# RGB_Camera.net
KiCad netlist of a schematic drawn in Altium Designer
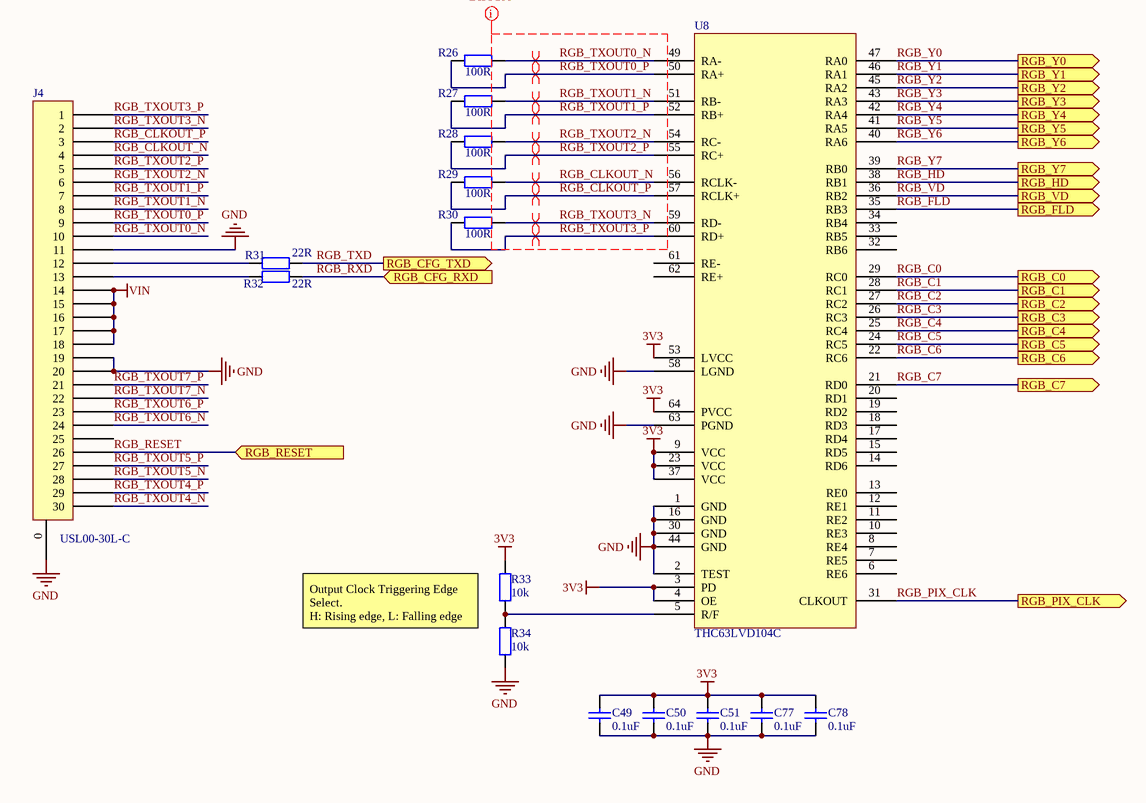
[diagram p0: RGB_Camera.SchDoc]

(export (version "E")
  (design (tool "Eeschema 10.0.6"))
  (components
    (comp (ref "C49")
      (value "GRM155R71C104KA88D")
      (footprint "0402C_M")
      (description "CAP CER 0.1UF 16V X7R 0402")
      (fields
        (field (name "MANUFACTURER") "Murata Electronics North America")
        (field (name "TOLERANCE") "±10%")
        (field (name "CAPACITANCE") "0.1uF")
      )
      (libsource (lib "KMTI-main") (part "GRM155R71C104KA88D"))
    )
    (comp (ref "C50")
      (value "GRM155R71C104KA88D")
      (footprint "0402C_M")
      (description "CAP CER 0.1UF 16V X7R 0402")
      (fields
        (field (name "MANUFACTURER") "Murata Electronics North America")
        (field (name "TOLERANCE") "±10%")
        (field (name "CAPACITANCE") "0.1uF")
      )
      (libsource (lib "KMTI-main") (part "GRM155R71C104KA88D"))
    )
    (comp (ref "C51")
      (value "GRM155R71C104KA88D")
      (footprint "0402C_M")
      (description "CAP CER 0.1UF 16V X7R 0402")
      (fields
        (field (name "MANUFACTURER") "Murata Electronics North America")
        (field (name "TOLERANCE") "±10%")
        (field (name "CAPACITANCE") "0.1uF")
      )
      (libsource (lib "KMTI-main") (part "GRM155R71C104KA88D"))
    )
    (comp (ref "C77")
      (value "GRM155R71C104KA88D")
      (footprint "0402C_M")
      (description "CAP CER 0.1UF 16V X7R 0402")
      (fields
        (field (name "MANUFACTURER") "Murata Electronics North America")
        (field (name "TOLERANCE") "±10%")
        (field (name "CAPACITANCE") "0.1uF")
      )
      (libsource (lib "KMTI-main") (part "GRM155R71C104KA88D"))
    )
    (comp (ref "C78")
      (value "GRM155R71C104KA88D")
      (footprint "0402C_M")
      (description "CAP CER 0.1UF 16V X7R 0402")
      (fields
        (field (name "MANUFACTURER") "Murata Electronics North America")
        (field (name "TOLERANCE") "±10%")
        (field (name "CAPACITANCE") "0.1uF")
      )
      (libsource (lib "KMTI-main") (part "GRM155R71C104KA88D"))
    )
    (comp (ref "J4")
      (value "USL00-30L-C")
      (footprint "USL00-30L-C")
      (libsource (lib "KMTI-main") (part "USL00-30L-C"))
    )
    (comp (ref "R26")
      (value "100R")
      (footprint "0402R_M")
      (description "RES SMD 100 OHM 1% 1/16W 0402")
      (fields
        (field (name "MANUFACTURER") "Vishay Dale")
        (field (name "MANUFACTURER PART NUMBER") "CRCW0402100RFKEE")
      )
      (libsource (lib "KMTI-main") (part "CRCW0402100RFKEE"))
    )
    (comp (ref "R27")
      (value "100R")
      (footprint "0402R_M")
      (description "RES SMD 100 OHM 1% 1/16W 0402")
      (fields
        (field (name "MANUFACTURER") "Vishay Dale")
        (field (name "MANUFACTURER PART NUMBER") "CRCW0402100RFKEE")
      )
      (libsource (lib "KMTI-main") (part "CRCW0402100RFKEE"))
    )
    (comp (ref "R28")
      (value "100R")
      (footprint "0402R_M")
      (description "RES SMD 100 OHM 1% 1/16W 0402")
      (fields
        (field (name "MANUFACTURER") "Vishay Dale")
        (field (name "MANUFACTURER PART NUMBER") "CRCW0402100RFKEE")
      )
      (libsource (lib "KMTI-main") (part "CRCW0402100RFKEE"))
    )
    (comp (ref "R29")
      (value "100R")
      (footprint "0402R_M")
      (description "RES SMD 100 OHM 1% 1/16W 0402")
      (fields
        (field (name "MANUFACTURER") "Vishay Dale")
        (field (name "MANUFACTURER PART NUMBER") "CRCW0402100RFKEE")
      )
      (libsource (lib "KMTI-main") (part "CRCW0402100RFKEE"))
    )
    (comp (ref "R30")
      (value "100R")
      (footprint "0402R_M")
      (description "RES SMD 100 OHM 1% 1/16W 0402")
      (fields
        (field (name "MANUFACTURER") "Vishay Dale")
        (field (name "MANUFACTURER PART NUMBER") "CRCW0402100RFKEE")
      )
      (libsource (lib "KMTI-main") (part "CRCW0402100RFKEE"))
    )
    (comp (ref "R31")
      (value "CRCW040222R0JNED")
      (footprint "0402R_M")
      (description "RES SMD 22 OHM 5% 1/16W 0402")
      (fields
        (field (name "MANUFACTURER") "Vishay / Dale")
        (field (name "TOLERANCE") "5 %")
        (field (name "RESISTANCE") "22R")
      )
      (libsource (lib "KMTI-main") (part "CRCW040222R0JNED"))
    )
    (comp (ref "R32")
      (value "CRCW040222R0JNED")
      (footprint "0402R_M")
      (description "RES SMD 22 OHM 5% 1/16W 0402")
      (fields
        (field (name "MANUFACTURER") "Vishay / Dale")
        (field (name "TOLERANCE") "5 %")
        (field (name "RESISTANCE") "22R")
      )
      (libsource (lib "KMTI-main") (part "CRCW040222R0JNED"))
    )
    (comp (ref "R33")
      (value "10k")
      (footprint "0402R_M")
      (description "RES SMD 10K OHM 1% 1/16W 0402")
      (fields
        (field (name "MANUFACTURER") "Vishay Dale")
        (field (name "MANUFACTURER PART NUMBER") "CRCW040210K0FKED")
      )
      (libsource (lib "KMTI-main") (part "CRCW040210K0FKED"))
    )
    (comp (ref "R34")
      (value "10k")
      (footprint "0402R_M")
      (description "RES SMD 10K OHM 1% 1/16W 0402")
      (fields
        (field (name "MANUFACTURER") "Vishay Dale")
        (field (name "MANUFACTURER PART NUMBER") "CRCW040210K0FKED")
      )
      (libsource (lib "KMTI-main") (part "CRCW040210K0FKED"))
    )
    (comp (ref "U8")
      (value "THC63LVD104C")
      (footprint "THC_LQFP64_L")
      (description "IC DESERIALIZER SNGL LVDS 64TQFP")
      (fields (field (name "MANUFACTURER") "CEL"))
      (libsource (lib "KMTI-main") (part "THC63LVD104C"))
    )
  )
  (nets
    (net (code "1") (name "/RGB_C0") (class "Default")
      (node (ref "U8") (pin "29") (pinfunction "RC0_29") (pintype "passive"))
    )
    (net (code "2") (name "/RGB_C1") (class "Default")
      (node (ref "U8") (pin "28") (pinfunction "RC1_28") (pintype "passive"))
    )
    (net (code "3") (name "/RGB_C2") (class "Default")
      (node (ref "U8") (pin "27") (pinfunction "RC2_27") (pintype "passive"))
    )
    (net (code "4") (name "/RGB_C3") (class "Default")
      (node (ref "U8") (pin "26") (pinfunction "RC3_26") (pintype "passive"))
    )
    (net (code "5") (name "/RGB_C4") (class "Default")
      (node (ref "U8") (pin "25") (pinfunction "RC4_25") (pintype "passive"))
    )
    (net (code "6") (name "/RGB_C5") (class "Default")
      (node (ref "U8") (pin "24") (pinfunction "RC5_24") (pintype "passive"))
    )
    (net (code "7") (name "/RGB_C6") (class "Default")
      (node (ref "U8") (pin "22") (pinfunction "RC6_22") (pintype "passive"))
    )
    (net (code "8") (name "/RGB_C7") (class "Default")
      (node (ref "U8") (pin "21") (pinfunction "RD0_21") (pintype "passive"))
    )
    (net (code "9") (name "/RGB_CLKOUT_N") (class "Default")
      (node (ref "J4") (pin "4") (pinfunction "4_4") (pintype "passive"))
      (node (ref "R29") (pin "2") (pinfunction "2_2") (pintype "passive"))
      (node (ref "U8") (pin "56") (pinfunction "RCLK-_56") (pintype "passive"))
    )
    (net (code "10") (name "/RGB_CLKOUT_P") (class "Default")
      (node (ref "J4") (pin "3") (pinfunction "3_3") (pintype "passive"))
      (node (ref "R29") (pin "1") (pinfunction "1_1") (pintype "passive"))
      (node (ref "U8") (pin "57") (pinfunction "RCLK+_57") (pintype "passive"))
    )
    (net (code "11") (name "/RGB_FLD") (class "Default")
      (node (ref "U8") (pin "35") (pinfunction "RB3_35") (pintype "passive"))
    )
    (net (code "12") (name "/RGB_HD") (class "Default")
      (node (ref "U8") (pin "38") (pinfunction "RB1_38") (pintype "passive"))
    )
    (net (code "13") (name "/RGB_PIX_CLK") (class "Default")
      (node (ref "U8") (pin "31") (pinfunction "CLKOUT_31") (pintype "passive"))
    )
    (net (code "14") (name "/RGB_RESET") (class "Default")
      (node (ref "J4") (pin "26") (pinfunction "26_26") (pintype "passive"))
    )
    (net (code "15") (name "/RGB_RXD") (class "Default")
      (node (ref "R32") (pin "2") (pinfunction "2_2") (pintype "passive"))
    )
    (net (code "16") (name "/RGB_TXD") (class "Default")
      (node (ref "R31") (pin "2") (pinfunction "2_2") (pintype "passive"))
    )
    (net (code "17") (name "/RGB_TXOUT0_N") (class "Default")
      (node (ref "J4") (pin "10") (pinfunction "10_10") (pintype "passive"))
      (node (ref "R26") (pin "2") (pinfunction "2_2") (pintype "passive"))
      (node (ref "U8") (pin "49") (pinfunction "RA-_49") (pintype "passive"))
    )
    (net (code "18") (name "/RGB_TXOUT0_P") (class "Default")
      (node (ref "J4") (pin "9") (pinfunction "9_9") (pintype "passive"))
      (node (ref "R26") (pin "1") (pinfunction "1_1") (pintype "passive"))
      (node (ref "U8") (pin "50") (pinfunction "RA+_50") (pintype "passive"))
    )
    (net (code "19") (name "/RGB_TXOUT1_N") (class "Default")
      (node (ref "J4") (pin "8") (pinfunction "8_8") (pintype "passive"))
      (node (ref "R27") (pin "2") (pinfunction "2_2") (pintype "passive"))
      (node (ref "U8") (pin "51") (pinfunction "RB-_51") (pintype "passive"))
    )
    (net (code "20") (name "/RGB_TXOUT1_P") (class "Default")
      (node (ref "J4") (pin "7") (pinfunction "7_7") (pintype "passive"))
      (node (ref "R27") (pin "1") (pinfunction "1_1") (pintype "passive"))
      (node (ref "U8") (pin "52") (pinfunction "RB+_52") (pintype "passive"))
    )
    (net (code "21") (name "/RGB_TXOUT2_N") (class "Default")
      (node (ref "J4") (pin "6") (pinfunction "6_6") (pintype "passive"))
      (node (ref "R28") (pin "2") (pinfunction "2_2") (pintype "passive"))
      (node (ref "U8") (pin "54") (pinfunction "RC-_54") (pintype "passive"))
    )
    (net (code "22") (name "/RGB_TXOUT2_P") (class "Default")
      (node (ref "J4") (pin "5") (pinfunction "5_5") (pintype "passive"))
      (node (ref "R28") (pin "1") (pinfunction "1_1") (pintype "passive"))
      (node (ref "U8") (pin "55") (pinfunction "RC+_55") (pintype "passive"))
    )
    (net (code "23") (name "/RGB_TXOUT3_N") (class "Default")
      (node (ref "J4") (pin "2") (pinfunction "2_2") (pintype "passive"))
      (node (ref "R30") (pin "2") (pinfunction "2_2") (pintype "passive"))
      (node (ref "U8") (pin "59") (pinfunction "RD-_59") (pintype "passive"))
    )
    (net (code "24") (name "/RGB_TXOUT3_P") (class "Default")
      (node (ref "J4") (pin "1") (pinfunction "1_1") (pintype "passive"))
      (node (ref "R30") (pin "1") (pinfunction "1_1") (pintype "passive"))
      (node (ref "U8") (pin "60") (pinfunction "RD+_60") (pintype "passive"))
    )
    (net (code "25") (name "/RGB_TXOUT4_N") (class "Default")
      (node (ref "J4") (pin "30") (pinfunction "30_30") (pintype "passive"))
    )
    (net (code "26") (name "/RGB_TXOUT4_P") (class "Default")
      (node (ref "J4") (pin "29") (pinfunction "29_29") (pintype "passive"))
    )
    (net (code "27") (name "/RGB_TXOUT5_N") (class "Default")
      (node (ref "J4") (pin "28") (pinfunction "28_28") (pintype "passive"))
    )
    (net (code "28") (name "/RGB_TXOUT5_P") (class "Default")
      (node (ref "J4") (pin "27") (pinfunction "27_27") (pintype "passive"))
    )
    (net (code "29") (name "/RGB_TXOUT6_N") (class "Default")
      (node (ref "J4") (pin "24") (pinfunction "24_24") (pintype "passive"))
    )
    (net (code "30") (name "/RGB_TXOUT6_P") (class "Default")
      (node (ref "J4") (pin "23") (pinfunction "23_23") (pintype "passive"))
    )
    (net (code "31") (name "/RGB_TXOUT7_N") (class "Default")
      (node (ref "J4") (pin "22") (pinfunction "22_22") (pintype "passive"))
    )
    (net (code "32") (name "/RGB_TXOUT7_P") (class "Default")
      (node (ref "J4") (pin "21") (pinfunction "21_21") (pintype "passive"))
    )
    (net (code "33") (name "/RGB_VD") (class "Default")
      (node (ref "U8") (pin "36") (pinfunction "RB2_36") (pintype "passive"))
    )
    (net (code "34") (name "/RGB_Y0") (class "Default")
      (node (ref "U8") (pin "47") (pinfunction "RA0_47") (pintype "passive"))
    )
    (net (code "35") (name "/RGB_Y1") (class "Default")
      (node (ref "U8") (pin "46") (pinfunction "RA1_46") (pintype "passive"))
    )
    (net (code "36") (name "/RGB_Y2") (class "Default")
      (node (ref "U8") (pin "45") (pinfunction "RA2_45") (pintype "passive"))
    )
    (net (code "37") (name "/RGB_Y3") (class "Default")
      (node (ref "U8") (pin "43") (pinfunction "RA3_43") (pintype "passive"))
    )
    (net (code "38") (name "/RGB_Y4") (class "Default")
      (node (ref "U8") (pin "42") (pinfunction "RA4_42") (pintype "passive"))
    )
    (net (code "39") (name "/RGB_Y5") (class "Default")
      (node (ref "U8") (pin "41") (pinfunction "RA5_41") (pintype "passive"))
    )
    (net (code "40") (name "/RGB_Y6") (class "Default")
      (node (ref "U8") (pin "40") (pinfunction "RA6_40") (pintype "passive"))
    )
    (net (code "41") (name "/RGB_Y7") (class "Default")
      (node (ref "U8") (pin "39") (pinfunction "RB0_39") (pintype "passive"))
    )
    (net (code "42") (name "3V3") (class "Default")
      (node (ref "C49") (pin "2") (pinfunction "2_2") (pintype "passive"))
      (node (ref "C50") (pin "2") (pinfunction "2_2") (pintype "passive"))
      (node (ref "C51") (pin "2") (pinfunction "2_2") (pintype "passive"))
      (node (ref "C77") (pin "2") (pinfunction "2_2") (pintype "passive"))
      (node (ref "C78") (pin "2") (pinfunction "2_2") (pintype "passive"))
      (node (ref "R33") (pin "2") (pinfunction "2_2") (pintype "passive"))
      (node (ref "U8") (pin "23") (pinfunction "VCC_23") (pintype "passive"))
      (node (ref "U8") (pin "3") (pinfunction "PD_3") (pintype "passive"))
      (node (ref "U8") (pin "37") (pinfunction "VCC_37") (pintype "passive"))
      (node (ref "U8") (pin "4") (pinfunction "OE_4") (pintype "passive"))
      (node (ref "U8") (pin "53") (pinfunction "LVCC_53") (pintype "passive"))
      (node (ref "U8") (pin "64") (pinfunction "PVCC_64") (pintype "passive"))
      (node (ref "U8") (pin "9") (pinfunction "VCC_9") (pintype "passive"))
    )
    (net (code "43") (name "GND") (class "Default")
      (node (ref "C49") (pin "1") (pinfunction "1_1") (pintype "passive"))
      (node (ref "C50") (pin "1") (pinfunction "1_1") (pintype "passive"))
      (node (ref "C51") (pin "1") (pinfunction "1_1") (pintype "passive"))
      (node (ref "C77") (pin "1") (pinfunction "1_1") (pintype "passive"))
      (node (ref "C78") (pin "1") (pinfunction "1_1") (pintype "passive"))
      (node (ref "J4") (pin "0") (pinfunction "0_0") (pintype "passive"))
      (node (ref "J4") (pin "11") (pinfunction "11_11") (pintype "passive"))
      (node (ref "J4") (pin "19") (pinfunction "19_19") (pintype "passive"))
      (node (ref "J4") (pin "20") (pinfunction "20_20") (pintype "passive"))
      (node (ref "R34") (pin "1") (pinfunction "1_1") (pintype "passive"))
      (node (ref "U8") (pin "1") (pinfunction "GND_1") (pintype "passive"))
      (node (ref "U8") (pin "16") (pinfunction "GND_16") (pintype "passive"))
      (node (ref "U8") (pin "2") (pinfunction "TEST_2") (pintype "passive"))
      (node (ref "U8") (pin "30") (pinfunction "GND_30") (pintype "passive"))
      (node (ref "U8") (pin "44") (pinfunction "GND_44") (pintype "passive"))
      (node (ref "U8") (pin "58") (pinfunction "LGND_58") (pintype "passive"))
      (node (ref "U8") (pin "63") (pinfunction "PGND_63") (pintype "passive"))
    )
    (net (code "44") (name "Net-(J4-Pad12)") (class "Default")
      (node (ref "J4") (pin "12") (pinfunction "12_12") (pintype "passive"))
      (node (ref "R31") (pin "1") (pinfunction "1_1") (pintype "passive"))
    )
    (net (code "45") (name "Net-(J4-Pad13)") (class "Default")
      (node (ref "J4") (pin "13") (pinfunction "13_13") (pintype "passive"))
      (node (ref "R32") (pin "1") (pinfunction "1_1") (pintype "passive"))
    )
    (net (code "46") (name "Net-(U8-R{slash}F)") (class "Default")
      (node (ref "R33") (pin "1") (pinfunction "1_1") (pintype "passive"))
      (node (ref "R34") (pin "2") (pinfunction "2_2") (pintype "passive"))
      (node (ref "U8") (pin "5") (pinfunction "R/F_5") (pintype "passive"))
    )
    (net (code "47") (name "VIN") (class "Default")
      (node (ref "J4") (pin "14") (pinfunction "14_14") (pintype "passive"))
      (node (ref "J4") (pin "15") (pinfunction "15_15") (pintype "passive"))
      (node (ref "J4") (pin "16") (pinfunction "16_16") (pintype "passive"))
      (node (ref "J4") (pin "17") (pinfunction "17_17") (pintype "passive"))
      (node (ref "J4") (pin "18") (pinfunction "18_18") (pintype "passive"))
    )
    (net (code "48") (name "unconnected-(J4-Pad25)") (class "Default")
      (node (ref "J4") (pin "25") (pinfunction "25_25") (pintype "passive"))
    )
    (net (code "49") (name "unconnected-(U8-RB4-Pad34)") (class "Default")
      (node (ref "U8") (pin "34") (pinfunction "RB4_34") (pintype "passive"))
    )
    (net (code "50") (name "unconnected-(U8-RB5-Pad33)") (class "Default")
      (node (ref "U8") (pin "33") (pinfunction "RB5_33") (pintype "passive"))
    )
    (net (code "51") (name "unconnected-(U8-RB6-Pad32)") (class "Default")
      (node (ref "U8") (pin "32") (pinfunction "RB6_32") (pintype "passive"))
    )
    (net (code "52") (name "unconnected-(U8-RD1-Pad20)") (class "Default")
      (node (ref "U8") (pin "20") (pinfunction "RD1_20") (pintype "passive"))
    )
    (net (code "53") (name "unconnected-(U8-RD2-Pad19)") (class "Default")
      (node (ref "U8") (pin "19") (pinfunction "RD2_19") (pintype "passive"))
    )
    (net (code "54") (name "unconnected-(U8-RD3-Pad18)") (class "Default")
      (node (ref "U8") (pin "18") (pinfunction "RD3_18") (pintype "passive"))
    )
    (net (code "55") (name "unconnected-(U8-RD4-Pad17)") (class "Default")
      (node (ref "U8") (pin "17") (pinfunction "RD4_17") (pintype "passive"))
    )
    (net (code "56") (name "unconnected-(U8-RD5-Pad15)") (class "Default")
      (node (ref "U8") (pin "15") (pinfunction "RD5_15") (pintype "passive"))
    )
    (net (code "57") (name "unconnected-(U8-RD6-Pad14)") (class "Default")
      (node (ref "U8") (pin "14") (pinfunction "RD6_14") (pintype "passive"))
    )
    (net (code "58") (name "unconnected-(U8-RE+-Pad62)") (class "Default")
      (node (ref "U8") (pin "62") (pinfunction "RE+_62") (pintype "passive"))
    )
    (net (code "59") (name "unconnected-(U8-RE--Pad61)") (class "Default")
      (node (ref "U8") (pin "61") (pinfunction "RE-_61") (pintype "passive"))
    )
    (net (code "60") (name "unconnected-(U8-RE0-Pad13)") (class "Default")
      (node (ref "U8") (pin "13") (pinfunction "RE0_13") (pintype "passive"))
    )
    (net (code "61") (name "unconnected-(U8-RE1-Pad12)") (class "Default")
      (node (ref "U8") (pin "12") (pinfunction "RE1_12") (pintype "passive"))
    )
    (net (code "62") (name "unconnected-(U8-RE2-Pad11)") (class "Default")
      (node (ref "U8") (pin "11") (pinfunction "RE2_11") (pintype "passive"))
    )
    (net (code "63") (name "unconnected-(U8-RE3-Pad10)") (class "Default")
      (node (ref "U8") (pin "10") (pinfunction "RE3_10") (pintype "passive"))
    )
    (net (code "64") (name "unconnected-(U8-RE4-Pad8)") (class "Default")
      (node (ref "U8") (pin "8") (pinfunction "RE4_8") (pintype "passive"))
    )
    (net (code "65") (name "unconnected-(U8-RE5-Pad7)") (class "Default")
      (node (ref "U8") (pin "7") (pinfunction "RE5_7") (pintype "passive"))
    )
    (net (code "66") (name "unconnected-(U8-RE6-Pad6)") (class "Default")
      (node (ref "U8") (pin "6") (pinfunction "RE6_6") (pintype "passive"))
    )
  )
)
